# SoC_Supply_GND.net
KiCad netlist of a schematic drawn in Altium Designer
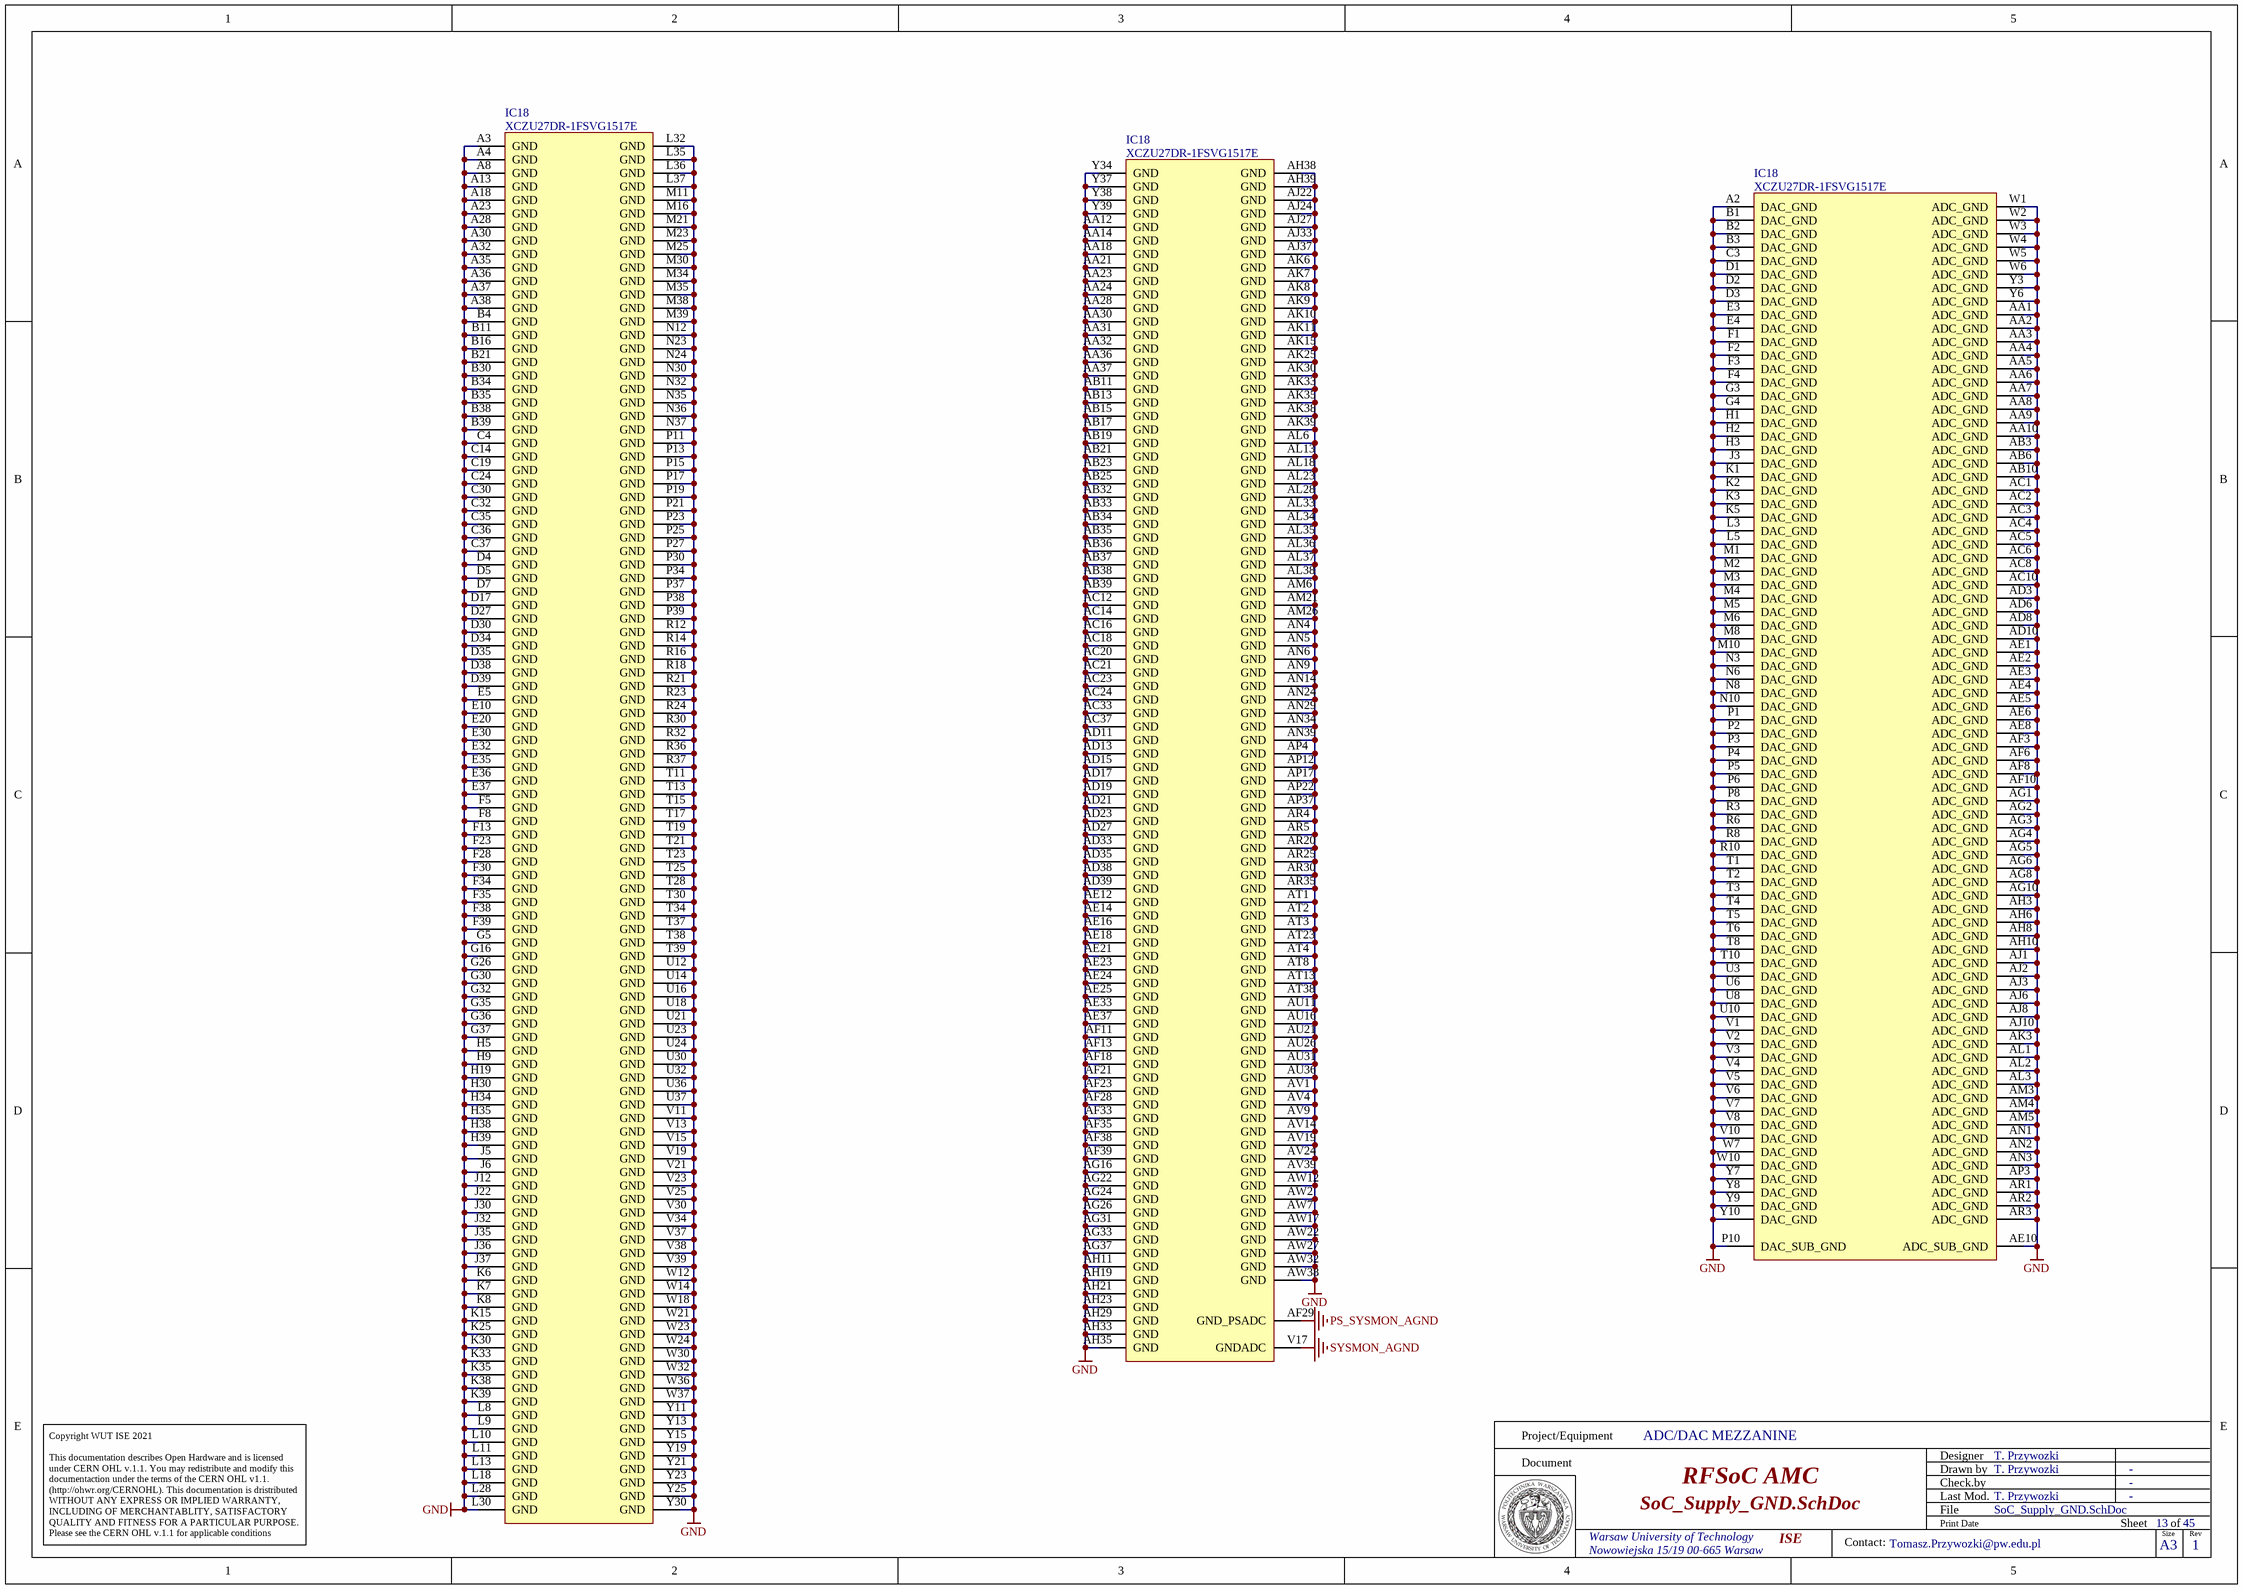
[diagram p0: SoC_Supply_GND.SchDoc]

(export (version "E")
  (design (tool "Eeschema 10.0.6"))
  (components
    (comp (ref "IC18")
      (value "XCZU27DR-1FSVG1517E")
      (footprint "XILINX_FSVG1517 (XCZU27DR)")
      (fields (field (name "MANUFACTURER") "XILINX") (field (name "AUTHOR") "CERN DEM MR"))
      (libsource (lib "ICs And Semiconductors") (part "XCZU27DR-1FSVG1517E"))
    )
  )
  (nets
    (net (code "1") (name "GND") (class "Default")
      (node (ref "IC18") (pin "A13") (pinfunction "GND_A13") (pintype "power_in"))
      (node (ref "IC18") (pin "A18") (pinfunction "GND_A18") (pintype "power_in"))
      (node (ref "IC18") (pin "A2") (pinfunction "DAC_GND_A2") (pintype "power_in"))
      (node (ref "IC18") (pin "A23") (pinfunction "GND_A23") (pintype "power_in"))
      (node (ref "IC18") (pin "A28") (pinfunction "GND_A28") (pintype "power_in"))
      (node (ref "IC18") (pin "A3") (pinfunction "GND_A3") (pintype "power_in"))
      (node (ref "IC18") (pin "A30") (pinfunction "GND_A30") (pintype "power_in"))
      (node (ref "IC18") (pin "A32") (pinfunction "GND_A32") (pintype "power_in"))
      (node (ref "IC18") (pin "A35") (pinfunction "GND_A35") (pintype "power_in"))
      (node (ref "IC18") (pin "A36") (pinfunction "GND_A36") (pintype "power_in"))
      (node (ref "IC18") (pin "A37") (pinfunction "GND_A37") (pintype "power_in"))
      (node (ref "IC18") (pin "A38") (pinfunction "GND_A38") (pintype "power_in"))
      (node (ref "IC18") (pin "A4") (pinfunction "GND_A4") (pintype "power_in"))
      (node (ref "IC18") (pin "A8") (pinfunction "GND_A8") (pintype "power_in"))
      (node (ref "IC18") (pin "AA1") (pinfunction "ADC_GND_AA1") (pintype "power_in"))
      (node (ref "IC18") (pin "AA10") (pinfunction "ADC_GND_AA10") (pintype "power_in"))
      (node (ref "IC18") (pin "AA12") (pinfunction "GND_AA12") (pintype "power_in"))
      (node (ref "IC18") (pin "AA14") (pinfunction "GND_AA14") (pintype "power_in"))
      (node (ref "IC18") (pin "AA18") (pinfunction "GND_AA18") (pintype "power_in"))
      (node (ref "IC18") (pin "AA2") (pinfunction "ADC_GND_AA2") (pintype "power_in"))
      (node (ref "IC18") (pin "AA21") (pinfunction "GND_AA21") (pintype "power_in"))
      (node (ref "IC18") (pin "AA23") (pinfunction "GND_AA23") (pintype "power_in"))
      (node (ref "IC18") (pin "AA24") (pinfunction "GND_AA24") (pintype "power_in"))
      (node (ref "IC18") (pin "AA28") (pinfunction "GND_AA28") (pintype "power_in"))
      (node (ref "IC18") (pin "AA3") (pinfunction "ADC_GND_AA3") (pintype "power_in"))
      (node (ref "IC18") (pin "AA30") (pinfunction "GND_AA30") (pintype "power_in"))
      (node (ref "IC18") (pin "AA31") (pinfunction "GND_AA31") (pintype "power_in"))
      (node (ref "IC18") (pin "AA32") (pinfunction "GND_AA32") (pintype "power_in"))
      (node (ref "IC18") (pin "AA36") (pinfunction "GND_AA36") (pintype "power_in"))
      (node (ref "IC18") (pin "AA37") (pinfunction "GND_AA37") (pintype "power_in"))
      (node (ref "IC18") (pin "AA4") (pinfunction "ADC_GND_AA4") (pintype "power_in"))
      (node (ref "IC18") (pin "AA5") (pinfunction "ADC_GND_AA5") (pintype "power_in"))
      (node (ref "IC18") (pin "AA6") (pinfunction "ADC_GND_AA6") (pintype "power_in"))
      (node (ref "IC18") (pin "AA7") (pinfunction "ADC_GND_AA7") (pintype "power_in"))
      (node (ref "IC18") (pin "AA8") (pinfunction "ADC_GND_AA8") (pintype "power_in"))
      (node (ref "IC18") (pin "AA9") (pinfunction "ADC_GND_AA9") (pintype "power_in"))
      (node (ref "IC18") (pin "AB10") (pinfunction "ADC_GND_AB10") (pintype "power_in"))
      (node (ref "IC18") (pin "AB11") (pinfunction "GND_AB11") (pintype "power_in"))
      (node (ref "IC18") (pin "AB13") (pinfunction "GND_AB13") (pintype "power_in"))
      (node (ref "IC18") (pin "AB15") (pinfunction "GND_AB15") (pintype "power_in"))
      (node (ref "IC18") (pin "AB17") (pinfunction "GND_AB17") (pintype "power_in"))
      (node (ref "IC18") (pin "AB19") (pinfunction "GND_AB19") (pintype "power_in"))
      (node (ref "IC18") (pin "AB21") (pinfunction "GND_AB21") (pintype "power_in"))
      (node (ref "IC18") (pin "AB23") (pinfunction "GND_AB23") (pintype "power_in"))
      (node (ref "IC18") (pin "AB25") (pinfunction "GND_AB25") (pintype "power_in"))
      (node (ref "IC18") (pin "AB3") (pinfunction "ADC_GND_AB3") (pintype "power_in"))
      (node (ref "IC18") (pin "AB32") (pinfunction "GND_AB32") (pintype "power_in"))
      (node (ref "IC18") (pin "AB33") (pinfunction "GND_AB33") (pintype "power_in"))
      (node (ref "IC18") (pin "AB34") (pinfunction "GND_AB34") (pintype "power_in"))
      (node (ref "IC18") (pin "AB35") (pinfunction "GND_AB35") (pintype "power_in"))
      (node (ref "IC18") (pin "AB36") (pinfunction "GND_AB36") (pintype "power_in"))
      (node (ref "IC18") (pin "AB37") (pinfunction "GND_AB37") (pintype "power_in"))
      (node (ref "IC18") (pin "AB38") (pinfunction "GND_AB38") (pintype "power_in"))
      (node (ref "IC18") (pin "AB39") (pinfunction "GND_AB39") (pintype "power_in"))
      (node (ref "IC18") (pin "AB6") (pinfunction "ADC_GND_AB6") (pintype "power_in"))
      (node (ref "IC18") (pin "AC1") (pinfunction "ADC_GND_AC1") (pintype "power_in"))
      (node (ref "IC18") (pin "AC10") (pinfunction "ADC_GND_AC10") (pintype "power_in"))
      (node (ref "IC18") (pin "AC12") (pinfunction "GND_AC12") (pintype "power_in"))
      (node (ref "IC18") (pin "AC14") (pinfunction "GND_AC14") (pintype "power_in"))
      (node (ref "IC18") (pin "AC16") (pinfunction "GND_AC16") (pintype "power_in"))
      (node (ref "IC18") (pin "AC18") (pinfunction "GND_AC18") (pintype "power_in"))
      (node (ref "IC18") (pin "AC2") (pinfunction "ADC_GND_AC2") (pintype "power_in"))
      (node (ref "IC18") (pin "AC20") (pinfunction "GND_AC20") (pintype "power_in"))
      (node (ref "IC18") (pin "AC21") (pinfunction "GND_AC21") (pintype "power_in"))
      (node (ref "IC18") (pin "AC23") (pinfunction "GND_AC23") (pintype "power_in"))
      (node (ref "IC18") (pin "AC24") (pinfunction "GND_AC24") (pintype "power_in"))
      (node (ref "IC18") (pin "AC3") (pinfunction "ADC_GND_AC3") (pintype "power_in"))
      (node (ref "IC18") (pin "AC33") (pinfunction "GND_AC33") (pintype "power_in"))
      (node (ref "IC18") (pin "AC37") (pinfunction "GND_AC37") (pintype "power_in"))
      (node (ref "IC18") (pin "AC4") (pinfunction "ADC_GND_AC4") (pintype "power_in"))
      (node (ref "IC18") (pin "AC5") (pinfunction "ADC_GND_AC5") (pintype "power_in"))
      (node (ref "IC18") (pin "AC6") (pinfunction "ADC_GND_AC6") (pintype "power_in"))
      (node (ref "IC18") (pin "AC8") (pinfunction "ADC_GND_AC8") (pintype "power_in"))
      (node (ref "IC18") (pin "AD10") (pinfunction "ADC_GND_AD10") (pintype "power_in"))
      (node (ref "IC18") (pin "AD11") (pinfunction "GND_AD11") (pintype "power_in"))
      (node (ref "IC18") (pin "AD13") (pinfunction "GND_AD13") (pintype "power_in"))
      (node (ref "IC18") (pin "AD15") (pinfunction "GND_AD15") (pintype "power_in"))
      (node (ref "IC18") (pin "AD17") (pinfunction "GND_AD17") (pintype "power_in"))
      (node (ref "IC18") (pin "AD19") (pinfunction "GND_AD19") (pintype "power_in"))
      (node (ref "IC18") (pin "AD21") (pinfunction "GND_AD21") (pintype "power_in"))
      (node (ref "IC18") (pin "AD23") (pinfunction "GND_AD23") (pintype "power_in"))
      (node (ref "IC18") (pin "AD27") (pinfunction "GND_AD27") (pintype "power_in"))
      (node (ref "IC18") (pin "AD3") (pinfunction "ADC_GND_AD3") (pintype "power_in"))
      (node (ref "IC18") (pin "AD33") (pinfunction "GND_AD33") (pintype "power_in"))
      (node (ref "IC18") (pin "AD35") (pinfunction "GND_AD35") (pintype "power_in"))
      (node (ref "IC18") (pin "AD38") (pinfunction "GND_AD38") (pintype "power_in"))
      (node (ref "IC18") (pin "AD39") (pinfunction "GND_AD39") (pintype "power_in"))
      (node (ref "IC18") (pin "AD6") (pinfunction "ADC_GND_AD6") (pintype "power_in"))
      (node (ref "IC18") (pin "AD8") (pinfunction "ADC_GND_AD8") (pintype "power_in"))
      (node (ref "IC18") (pin "AE1") (pinfunction "ADC_GND_AE1") (pintype "power_in"))
      (node (ref "IC18") (pin "AE10") (pinfunction "ADC_SUB_GND_AE10") (pintype "power_in"))
      (node (ref "IC18") (pin "AE12") (pinfunction "GND_AE12") (pintype "power_in"))
      (node (ref "IC18") (pin "AE14") (pinfunction "GND_AE14") (pintype "power_in"))
      (node (ref "IC18") (pin "AE16") (pinfunction "GND_AE16") (pintype "power_in"))
      (node (ref "IC18") (pin "AE18") (pinfunction "GND_AE18") (pintype "power_in"))
      (node (ref "IC18") (pin "AE2") (pinfunction "ADC_GND_AE2") (pintype "power_in"))
      (node (ref "IC18") (pin "AE21") (pinfunction "GND_AE21") (pintype "power_in"))
      (node (ref "IC18") (pin "AE23") (pinfunction "GND_AE23") (pintype "power_in"))
      (node (ref "IC18") (pin "AE24") (pinfunction "GND_AE24") (pintype "power_in"))
      (node (ref "IC18") (pin "AE25") (pinfunction "GND_AE25") (pintype "power_in"))
      (node (ref "IC18") (pin "AE3") (pinfunction "ADC_GND_AE3") (pintype "power_in"))
      (node (ref "IC18") (pin "AE33") (pinfunction "GND_AE33") (pintype "power_in"))
      (node (ref "IC18") (pin "AE37") (pinfunction "GND_AE37") (pintype "power_in"))
      (node (ref "IC18") (pin "AE4") (pinfunction "ADC_GND_AE4") (pintype "power_in"))
      (node (ref "IC18") (pin "AE5") (pinfunction "ADC_GND_AE5") (pintype "power_in"))
      (node (ref "IC18") (pin "AE6") (pinfunction "ADC_GND_AE6") (pintype "power_in"))
      (node (ref "IC18") (pin "AE8") (pinfunction "ADC_GND_AE8") (pintype "power_in"))
      (node (ref "IC18") (pin "AF10") (pinfunction "ADC_GND_AF10") (pintype "power_in"))
      (node (ref "IC18") (pin "AF11") (pinfunction "GND_AF11") (pintype "power_in"))
      (node (ref "IC18") (pin "AF13") (pinfunction "GND_AF13") (pintype "power_in"))
      (node (ref "IC18") (pin "AF18") (pinfunction "GND_AF18") (pintype "power_in"))
      (node (ref "IC18") (pin "AF21") (pinfunction "GND_AF21") (pintype "power_in"))
      (node (ref "IC18") (pin "AF23") (pinfunction "GND_AF23") (pintype "power_in"))
      (node (ref "IC18") (pin "AF28") (pinfunction "GND_AF28") (pintype "power_in"))
      (node (ref "IC18") (pin "AF3") (pinfunction "ADC_GND_AF3") (pintype "power_in"))
      (node (ref "IC18") (pin "AF33") (pinfunction "GND_AF33") (pintype "power_in"))
      (node (ref "IC18") (pin "AF35") (pinfunction "GND_AF35") (pintype "power_in"))
      (node (ref "IC18") (pin "AF38") (pinfunction "GND_AF38") (pintype "power_in"))
      (node (ref "IC18") (pin "AF39") (pinfunction "GND_AF39") (pintype "power_in"))
      (node (ref "IC18") (pin "AF6") (pinfunction "ADC_GND_AF6") (pintype "power_in"))
      (node (ref "IC18") (pin "AF8") (pinfunction "ADC_GND_AF8") (pintype "power_in"))
      (node (ref "IC18") (pin "AG1") (pinfunction "ADC_GND_AG1") (pintype "power_in"))
      (node (ref "IC18") (pin "AG10") (pinfunction "ADC_GND_AG10") (pintype "power_in"))
      (node (ref "IC18") (pin "AG16") (pinfunction "GND_AG16") (pintype "power_in"))
      (node (ref "IC18") (pin "AG2") (pinfunction "ADC_GND_AG2") (pintype "power_in"))
      (node (ref "IC18") (pin "AG22") (pinfunction "GND_AG22") (pintype "power_in"))
      (node (ref "IC18") (pin "AG24") (pinfunction "GND_AG24") (pintype "power_in"))
      (node (ref "IC18") (pin "AG26") (pinfunction "GND_AG26") (pintype "power_in"))
      (node (ref "IC18") (pin "AG3") (pinfunction "ADC_GND_AG3") (pintype "power_in"))
      (node (ref "IC18") (pin "AG31") (pinfunction "GND_AG31") (pintype "power_in"))
      (node (ref "IC18") (pin "AG33") (pinfunction "GND_AG33") (pintype "power_in"))
      (node (ref "IC18") (pin "AG37") (pinfunction "GND_AG37") (pintype "power_in"))
      (node (ref "IC18") (pin "AG4") (pinfunction "ADC_GND_AG4") (pintype "power_in"))
      (node (ref "IC18") (pin "AG5") (pinfunction "ADC_GND_AG5") (pintype "power_in"))
      (node (ref "IC18") (pin "AG6") (pinfunction "ADC_GND_AG6") (pintype "power_in"))
      (node (ref "IC18") (pin "AG8") (pinfunction "ADC_GND_AG8") (pintype "power_in"))
      (node (ref "IC18") (pin "AH10") (pinfunction "ADC_GND_AH10") (pintype "power_in"))
      (node (ref "IC18") (pin "AH11") (pinfunction "GND_AH11") (pintype "power_in"))
      (node (ref "IC18") (pin "AH19") (pinfunction "GND_AH19") (pintype "power_in"))
      (node (ref "IC18") (pin "AH21") (pinfunction "GND_AH21") (pintype "power_in"))
      (node (ref "IC18") (pin "AH23") (pinfunction "GND_AH23") (pintype "power_in"))
      (node (ref "IC18") (pin "AH29") (pinfunction "GND_AH29") (pintype "power_in"))
      (node (ref "IC18") (pin "AH3") (pinfunction "ADC_GND_AH3") (pintype "power_in"))
      (node (ref "IC18") (pin "AH33") (pinfunction "GND_AH33") (pintype "power_in"))
      (node (ref "IC18") (pin "AH35") (pinfunction "GND_AH35") (pintype "power_in"))
      (node (ref "IC18") (pin "AH38") (pinfunction "GND_AH38") (pintype "power_in"))
      (node (ref "IC18") (pin "AH39") (pinfunction "GND_AH39") (pintype "power_in"))
      (node (ref "IC18") (pin "AH6") (pinfunction "ADC_GND_AH6") (pintype "power_in"))
      (node (ref "IC18") (pin "AH8") (pinfunction "ADC_GND_AH8") (pintype "power_in"))
      (node (ref "IC18") (pin "AJ1") (pinfunction "ADC_GND_AJ1") (pintype "power_in"))
      (node (ref "IC18") (pin "AJ10") (pinfunction "ADC_GND_AJ10") (pintype "power_in"))
      (node (ref "IC18") (pin "AJ2") (pinfunction "ADC_GND_AJ2") (pintype "power_in"))
      (node (ref "IC18") (pin "AJ22") (pinfunction "GND_AJ22") (pintype "power_in"))
      (node (ref "IC18") (pin "AJ24") (pinfunction "GND_AJ24") (pintype "power_in"))
      (node (ref "IC18") (pin "AJ27") (pinfunction "GND_AJ27") (pintype "power_in"))
      (node (ref "IC18") (pin "AJ3") (pinfunction "ADC_GND_AJ3") (pintype "power_in"))
      (node (ref "IC18") (pin "AJ33") (pinfunction "GND_AJ33") (pintype "power_in"))
      (node (ref "IC18") (pin "AJ37") (pinfunction "GND_AJ37") (pintype "power_in"))
      (node (ref "IC18") (pin "AJ6") (pinfunction "ADC_GND_AJ6") (pintype "power_in"))
      (node (ref "IC18") (pin "AJ8") (pinfunction "ADC_GND_AJ8") (pintype "power_in"))
      (node (ref "IC18") (pin "AK10") (pinfunction "GND_AK10") (pintype "power_in"))
      (node (ref "IC18") (pin "AK11") (pinfunction "GND_AK11") (pintype "power_in"))
      (node (ref "IC18") (pin "AK15") (pinfunction "GND_AK15") (pintype "power_in"))
      (node (ref "IC18") (pin "AK25") (pinfunction "GND_AK25") (pintype "power_in"))
      (node (ref "IC18") (pin "AK3") (pinfunction "ADC_GND_AK3") (pintype "power_in"))
      (node (ref "IC18") (pin "AK30") (pinfunction "GND_AK30") (pintype "power_in"))
      (node (ref "IC18") (pin "AK33") (pinfunction "GND_AK33") (pintype "power_in"))
      (node (ref "IC18") (pin "AK35") (pinfunction "GND_AK35") (pintype "power_in"))
      (node (ref "IC18") (pin "AK38") (pinfunction "GND_AK38") (pintype "power_in"))
      (node (ref "IC18") (pin "AK39") (pinfunction "GND_AK39") (pintype "power_in"))
      (node (ref "IC18") (pin "AK6") (pinfunction "GND_AK6") (pintype "power_in"))
      (node (ref "IC18") (pin "AK7") (pinfunction "GND_AK7") (pintype "power_in"))
      (node (ref "IC18") (pin "AK8") (pinfunction "GND_AK8") (pintype "power_in"))
      (node (ref "IC18") (pin "AK9") (pinfunction "GND_AK9") (pintype "power_in"))
      (node (ref "IC18") (pin "AL1") (pinfunction "ADC_GND_AL1") (pintype "power_in"))
      (node (ref "IC18") (pin "AL13") (pinfunction "GND_AL13") (pintype "power_in"))
      (node (ref "IC18") (pin "AL18") (pinfunction "GND_AL18") (pintype "power_in"))
      (node (ref "IC18") (pin "AL2") (pinfunction "ADC_GND_AL2") (pintype "power_in"))
      (node (ref "IC18") (pin "AL23") (pinfunction "GND_AL23") (pintype "power_in"))
      (node (ref "IC18") (pin "AL28") (pinfunction "GND_AL28") (pintype "power_in"))
      (node (ref "IC18") (pin "AL3") (pinfunction "ADC_GND_AL3") (pintype "power_in"))
      (node (ref "IC18") (pin "AL33") (pinfunction "GND_AL33") (pintype "power_in"))
      (node (ref "IC18") (pin "AL34") (pinfunction "GND_AL34") (pintype "power_in"))
      (node (ref "IC18") (pin "AL35") (pinfunction "GND_AL35") (pintype "power_in"))
      (node (ref "IC18") (pin "AL36") (pinfunction "GND_AL36") (pintype "power_in"))
      (node (ref "IC18") (pin "AL37") (pinfunction "GND_AL37") (pintype "power_in"))
      (node (ref "IC18") (pin "AL38") (pinfunction "GND_AL38") (pintype "power_in"))
      (node (ref "IC18") (pin "AL6") (pinfunction "GND_AL6") (pintype "power_in"))
      (node (ref "IC18") (pin "AM21") (pinfunction "GND_AM21") (pintype "power_in"))
      (node (ref "IC18") (pin "AM26") (pinfunction "GND_AM26") (pintype "power_in"))
      (node (ref "IC18") (pin "AM3") (pinfunction "ADC_GND_AM3") (pintype "power_in"))
      (node (ref "IC18") (pin "AM4") (pinfunction "ADC_GND_AM4") (pintype "power_in"))
      (node (ref "IC18") (pin "AM5") (pinfunction "ADC_GND_AM5") (pintype "power_in"))
      (node (ref "IC18") (pin "AM6") (pinfunction "GND_AM6") (pintype "power_in"))
      (node (ref "IC18") (pin "AN1") (pinfunction "ADC_GND_AN1") (pintype "power_in"))
      (node (ref "IC18") (pin "AN14") (pinfunction "GND_AN14") (pintype "power_in"))
      (node (ref "IC18") (pin "AN2") (pinfunction "ADC_GND_AN2") (pintype "power_in"))
      (node (ref "IC18") (pin "AN24") (pinfunction "GND_AN24") (pintype "power_in"))
      (node (ref "IC18") (pin "AN29") (pinfunction "GND_AN29") (pintype "power_in"))
      (node (ref "IC18") (pin "AN3") (pinfunction "ADC_GND_AN3") (pintype "power_in"))
      (node (ref "IC18") (pin "AN34") (pinfunction "GND_AN34") (pintype "power_in"))
      (node (ref "IC18") (pin "AN39") (pinfunction "GND_AN39") (pintype "power_in"))
      (node (ref "IC18") (pin "AN4") (pinfunction "GND_AN4") (pintype "power_in"))
      (node (ref "IC18") (pin "AN5") (pinfunction "GND_AN5") (pintype "power_in"))
      (node (ref "IC18") (pin "AN6") (pinfunction "GND_AN6") (pintype "power_in"))
      (node (ref "IC18") (pin "AN9") (pinfunction "GND_AN9") (pintype "power_in"))
      (node (ref "IC18") (pin "AP12") (pinfunction "GND_AP12") (pintype "power_in"))
      (node (ref "IC18") (pin "AP17") (pinfunction "GND_AP17") (pintype "power_in"))
      (node (ref "IC18") (pin "AP22") (pinfunction "GND_AP22") (pintype "power_in"))
      (node (ref "IC18") (pin "AP3") (pinfunction "ADC_GND_AP3") (pintype "power_in"))
      (node (ref "IC18") (pin "AP37") (pinfunction "GND_AP37") (pintype "power_in"))
      (node (ref "IC18") (pin "AP4") (pinfunction "GND_AP4") (pintype "power_in"))
      (node (ref "IC18") (pin "AR1") (pinfunction "ADC_GND_AR1") (pintype "power_in"))
      (node (ref "IC18") (pin "AR2") (pinfunction "ADC_GND_AR2") (pintype "power_in"))
      (node (ref "IC18") (pin "AR20") (pinfunction "GND_AR20") (pintype "power_in"))
      (node (ref "IC18") (pin "AR25") (pinfunction "GND_AR25") (pintype "power_in"))
      (node (ref "IC18") (pin "AR3") (pinfunction "ADC_GND_AR3") (pintype "power_in"))
      (node (ref "IC18") (pin "AR30") (pinfunction "GND_AR30") (pintype "power_in"))
      (node (ref "IC18") (pin "AR35") (pinfunction "GND_AR35") (pintype "power_in"))
      (node (ref "IC18") (pin "AR4") (pinfunction "GND_AR4") (pintype "power_in"))
      (node (ref "IC18") (pin "AR5") (pinfunction "GND_AR5") (pintype "power_in"))
      (node (ref "IC18") (pin "AT1") (pinfunction "GND_AT1") (pintype "power_in"))
      (node (ref "IC18") (pin "AT13") (pinfunction "GND_AT13") (pintype "power_in"))
      (node (ref "IC18") (pin "AT2") (pinfunction "GND_AT2") (pintype "power_in"))
      (node (ref "IC18") (pin "AT23") (pinfunction "GND_AT23") (pintype "power_in"))
      (node (ref "IC18") (pin "AT3") (pinfunction "GND_AT3") (pintype "power_in"))
      (node (ref "IC18") (pin "AT38") (pinfunction "GND_AT38") (pintype "power_in"))
      (node (ref "IC18") (pin "AT4") (pinfunction "GND_AT4") (pintype "power_in"))
      (node (ref "IC18") (pin "AT8") (pinfunction "GND_AT8") (pintype "power_in"))
      (node (ref "IC18") (pin "AU11") (pinfunction "GND_AU11") (pintype "power_in"))
      (node (ref "IC18") (pin "AU16") (pinfunction "GND_AU16") (pintype "power_in"))
      (node (ref "IC18") (pin "AU21") (pinfunction "GND_AU21") (pintype "power_in"))
      (node (ref "IC18") (pin "AU26") (pinfunction "GND_AU26") (pintype "power_in"))
      (node (ref "IC18") (pin "AU31") (pinfunction "GND_AU31") (pintype "power_in"))
      (node (ref "IC18") (pin "AU36") (pinfunction "GND_AU36") (pintype "power_in"))
      (node (ref "IC18") (pin "AV1") (pinfunction "GND_AV1") (pintype "power_in"))
      (node (ref "IC18") (pin "AV14") (pinfunction "GND_AV14") (pintype "power_in"))
      (node (ref "IC18") (pin "AV19") (pinfunction "GND_AV19") (pintype "power_in"))
      (node (ref "IC18") (pin "AV24") (pinfunction "GND_AV24") (pintype "power_in"))
      (node (ref "IC18") (pin "AV39") (pinfunction "GND_AV39") (pintype "power_in"))
      (node (ref "IC18") (pin "AV4") (pinfunction "GND_AV4") (pintype "power_in"))
      (node (ref "IC18") (pin "AV9") (pinfunction "GND_AV9") (pintype "power_in"))
      (node (ref "IC18") (pin "AW12") (pinfunction "GND_AW12") (pintype "power_in"))
      (node (ref "IC18") (pin "AW17") (pinfunction "GND_AW17") (pintype "power_in"))
      (node (ref "IC18") (pin "AW2") (pinfunction "GND_AW2") (pintype "power_in"))
      (node (ref "IC18") (pin "AW22") (pinfunction "GND_AW22") (pintype "power_in"))
      (node (ref "IC18") (pin "AW27") (pinfunction "GND_AW27") (pintype "power_in"))
      (node (ref "IC18") (pin "AW32") (pinfunction "GND_AW32") (pintype "power_in"))
      (node (ref "IC18") (pin "AW38") (pinfunction "GND_AW38") (pintype "power_in"))
      (node (ref "IC18") (pin "AW7") (pinfunction "GND_AW7") (pintype "power_in"))
      (node (ref "IC18") (pin "B1") (pinfunction "DAC_GND_B1") (pintype "power_in"))
      (node (ref "IC18") (pin "B11") (pinfunction "GND_B11") (pintype "power_in"))
      (node (ref "IC18") (pin "B16") (pinfunction "GND_B16") (pintype "power_in"))
      (node (ref "IC18") (pin "B2") (pinfunction "DAC_GND_B2") (pintype "power_in"))
      (node (ref "IC18") (pin "B21") (pinfunction "GND_B21") (pintype "power_in"))
      (node (ref "IC18") (pin "B3") (pinfunction "DAC_GND_B3") (pintype "power_in"))
      (node (ref "IC18") (pin "B30") (pinfunction "GND_B30") (pintype "power_in"))
      (node (ref "IC18") (pin "B34") (pinfunction "GND_B34") (pintype "power_in"))
      (node (ref "IC18") (pin "B35") (pinfunction "GND_B35") (pintype "power_in"))
      (node (ref "IC18") (pin "B38") (pinfunction "GND_B38") (pintype "power_in"))
      (node (ref "IC18") (pin "B39") (pinfunction "GND_B39") (pintype "power_in"))
      (node (ref "IC18") (pin "B4") (pinfunction "GND_B4") (pintype "power_in"))
      (node (ref "IC18") (pin "C14") (pinfunction "GND_C14") (pintype "power_in"))
      (node (ref "IC18") (pin "C19") (pinfunction "GND_C19") (pintype "power_in"))
      (node (ref "IC18") (pin "C24") (pinfunction "GND_C24") (pintype "power_in"))
      (node (ref "IC18") (pin "C3") (pinfunction "DAC_GND_C3") (pintype "power_in"))
      (node (ref "IC18") (pin "C30") (pinfunction "GND_C30") (pintype "power_in"))
      (node (ref "IC18") (pin "C32") (pinfunction "GND_C32") (pintype "power_in"))
      (node (ref "IC18") (pin "C35") (pinfunction "GND_C35") (pintype "power_in"))
      (node (ref "IC18") (pin "C36") (pinfunction "GND_C36") (pintype "power_in"))
      (node (ref "IC18") (pin "C37") (pinfunction "GND_C37") (pintype "power_in"))
      (node (ref "IC18") (pin "C4") (pinfunction "GND_C4") (pintype "power_in"))
      (node (ref "IC18") (pin "D1") (pinfunction "DAC_GND_D1") (pintype "power_in"))
      (node (ref "IC18") (pin "D17") (pinfunction "GND_D17") (pintype "power_in"))
      (node (ref "IC18") (pin "D2") (pinfunction "DAC_GND_D2") (pintype "power_in"))
      (node (ref "IC18") (pin "D27") (pinfunction "GND_D27") (pintype "power_in"))
      (node (ref "IC18") (pin "D3") (pinfunction "DAC_GND_D3") (pintype "power_in"))
      (node (ref "IC18") (pin "D30") (pinfunction "GND_D30") (pintype "power_in"))
      (node (ref "IC18") (pin "D34") (pinfunction "GND_D34") (pintype "power_in"))
      (node (ref "IC18") (pin "D35") (pinfunction "GND_D35") (pintype "power_in"))
      (node (ref "IC18") (pin "D38") (pinfunction "GND_D38") (pintype "power_in"))
      (node (ref "IC18") (pin "D39") (pinfunction "GND_D39") (pintype "power_in"))
      (node (ref "IC18") (pin "D4") (pinfunction "GND_D4") (pintype "power_in"))
      (node (ref "IC18") (pin "D5") (pinfunction "GND_D5") (pintype "power_in"))
      (node (ref "IC18") (pin "D7") (pinfunction "GND_D7") (pintype "power_in"))
      (node (ref "IC18") (pin "E10") (pinfunction "GND_E10") (pintype "power_in"))
      (node (ref "IC18") (pin "E20") (pinfunction "GND_E20") (pintype "power_in"))
      (node (ref "IC18") (pin "E3") (pinfunction "DAC_GND_E3") (pintype "power_in"))
      (node (ref "IC18") (pin "E30") (pinfunction "GND_E30") (pintype "power_in"))
      (node (ref "IC18") (pin "E32") (pinfunction "GND_E32") (pintype "power_in"))
      (node (ref "IC18") (pin "E35") (pinfunction "GND_E35") (pintype "power_in"))
      (node (ref "IC18") (pin "E36") (pinfunction "GND_E36") (pintype "power_in"))
      (node (ref "IC18") (pin "E37") (pinfunction "GND_E37") (pintype "power_in"))
      (node (ref "IC18") (pin "E4") (pinfunction "DAC_GND_E4") (pintype "power_in"))
      (node (ref "IC18") (pin "E5") (pinfunction "GND_E5") (pintype "power_in"))
      (node (ref "IC18") (pin "F1") (pinfunction "DAC_GND_F1") (pintype "power_in"))
      (node (ref "IC18") (pin "F13") (pinfunction "GND_F13") (pintype "power_in"))
      (node (ref "IC18") (pin "F2") (pinfunction "DAC_GND_F2") (pintype "power_in"))
      (node (ref "IC18") (pin "F23") (pinfunction "GND_F23") (pintype "power_in"))
      (node (ref "IC18") (pin "F28") (pinfunction "GND_F28") (pintype "power_in"))
      (node (ref "IC18") (pin "F3") (pinfunction "DAC_GND_F3") (pintype "power_in"))
      (node (ref "IC18") (pin "F30") (pinfunction "GND_F30") (pintype "power_in"))
      (node (ref "IC18") (pin "F34") (pinfunction "GND_F34") (pintype "power_in"))
      (node (ref "IC18") (pin "F35") (pinfunction "GND_F35") (pintype "power_in"))
      (node (ref "IC18") (pin "F38") (pinfunction "GND_F38") (pintype "power_in"))
      (node (ref "IC18") (pin "F39") (pinfunction "GND_F39") (pintype "power_in"))
      (node (ref "IC18") (pin "F4") (pinfunction "DAC_GND_F4") (pintype "power_in"))
      (node (ref "IC18") (pin "F5") (pinfunction "GND_F5") (pintype "power_in"))
      (node (ref "IC18") (pin "F8") (pinfunction "GND_F8") (pintype "power_in"))
      (node (ref "IC18") (pin "G16") (pinfunction "GND_G16") (pintype "power_in"))
      (node (ref "IC18") (pin "G26") (pinfunction "GND_G26") (pintype "power_in"))
      (node (ref "IC18") (pin "G3") (pinfunction "DAC_GND_G3") (pintype "power_in"))
      (node (ref "IC18") (pin "G30") (pinfunction "GND_G30") (pintype "power_in"))
      (node (ref "IC18") (pin "G32") (pinfunction "GND_G32") (pintype "power_in"))
      (node (ref "IC18") (pin "G35") (pinfunction "GND_G35") (pintype "power_in"))
      (node (ref "IC18") (pin "G36") (pinfunction "GND_G36") (pintype "power_in"))
      (node (ref "IC18") (pin "G37") (pinfunction "GND_G37") (pintype "power_in"))
      (node (ref "IC18") (pin "G4") (pinfunction "DAC_GND_G4") (pintype "power_in"))
      (node (ref "IC18") (pin "G5") (pinfunction "GND_G5") (pintype "power_in"))
      (node (ref "IC18") (pin "H1") (pinfunction "DAC_GND_H1") (pintype "power_in"))
      (node (ref "IC18") (pin "H19") (pinfunction "GND_H19") (pintype "power_in"))
      (node (ref "IC18") (pin "H2") (pinfunction "DAC_GND_H2") (pintype "power_in"))
      (node (ref "IC18") (pin "H3") (pinfunction "DAC_GND_H3") (pintype "power_in"))
      (node (ref "IC18") (pin "H30") (pinfunction "GND_H30") (pintype "power_in"))
      (node (ref "IC18") (pin "H34") (pinfunction "GND_H34") (pintype "power_in"))
      (node (ref "IC18") (pin "H35") (pinfunction "GND_H35") (pintype "power_in"))
      (node (ref "IC18") (pin "H38") (pinfunction "GND_H38") (pintype "power_in"))
      (node (ref "IC18") (pin "H39") (pinfunction "GND_H39") (pintype "power_in"))
      (node (ref "IC18") (pin "H5") (pinfunction "GND_H5") (pintype "power_in"))
      (node (ref "IC18") (pin "H9") (pinfunction "GND_H9") (pintype "power_in"))
      (node (ref "IC18") (pin "J12") (pinfunction "GND_J12") (pintype "power_in"))
      (node (ref "IC18") (pin "J22") (pinfunction "GND_J22") (pintype "power_in"))
      (node (ref "IC18") (pin "J3") (pinfunction "DAC_GND_J3") (pintype "power_in"))
      (node (ref "IC18") (pin "J30") (pinfunction "GND_J30") (pintype "power_in"))
      (node (ref "IC18") (pin "J32") (pinfunction "GND_J32") (pintype "power_in"))
      (node (ref "IC18") (pin "J35") (pinfunction "GND_J35") (pintype "power_in"))
      (node (ref "IC18") (pin "J36") (pinfunction "GND_J36") (pintype "power_in"))
      (node (ref "IC18") (pin "J37") (pinfunction "GND_J37") (pintype "power_in"))
      (node (ref "IC18") (pin "J5") (pinfunction "GND_J5") (pintype "power_in"))
      (node (ref "IC18") (pin "J6") (pinfunction "GND_J6") (pintype "power_in"))
      (node (ref "IC18") (pin "K1") (pinfunction "DAC_GND_K1") (pintype "power_in"))
      (node (ref "IC18") (pin "K15") (pinfunction "GND_K15") (pintype "power_in"))
      (node (ref "IC18") (pin "K2") (pinfunction "DAC_GND_K2") (pintype "power_in"))
      (node (ref "IC18") (pin "K25") (pinfunction "GND_K25") (pintype "power_in"))
      (node (ref "IC18") (pin "K3") (pinfunction "DAC_GND_K3") (pintype "power_in"))
      (node (ref "IC18") (pin "K30") (pinfunction "GND_K30") (pintype "power_in"))
      (node (ref "IC18") (pin "K33") (pinfunction "GND_K33") (pintype "power_in"))
      (node (ref "IC18") (pin "K35") (pinfunction "GND_K35") (pintype "power_in"))
      (node (ref "IC18") (pin "K38") (pinfunction "GND_K38") (pintype "power_in"))
      (node (ref "IC18") (pin "K39") (pinfunction "GND_K39") (pintype "power_in"))
      (node (ref "IC18") (pin "K5") (pinfunction "DAC_GND_K5") (pintype "power_in"))
      (node (ref "IC18") (pin "K6") (pinfunction "GND_K6") (pintype "power_in"))
      (node (ref "IC18") (pin "K7") (pinfunction "GND_K7") (pintype "power_in"))
      (node (ref "IC18") (pin "K8") (pinfunction "GND_K8") (pintype "power_in"))
      (node (ref "IC18") (pin "L10") (pinfunction "GND_L10") (pintype "power_in"))
      (node (ref "IC18") (pin "L11") (pinfunction "GND_L11") (pintype "power_in"))
      (node (ref "IC18") (pin "L13") (pinfunction "GND_L13") (pintype "power_in"))
      (node (ref "IC18") (pin "L18") (pinfunction "GND_L18") (pintype "power_in"))
      (node (ref "IC18") (pin "L28") (pinfunction "GND_L28") (pintype "power_in"))
      (node (ref "IC18") (pin "L3") (pinfunction "DAC_GND_L3") (pintype "power_in"))
      (node (ref "IC18") (pin "L30") (pinfunction "GND_L30") (pintype "power_in"))
      (node (ref "IC18") (pin "L32") (pinfunction "GND_L32") (pintype "power_in"))
      (node (ref "IC18") (pin "L35") (pinfunction "GND_L35") (pintype "power_in"))
      (node (ref "IC18") (pin "L36") (pinfunction "GND_L36") (pintype "power_in"))
      (node (ref "IC18") (pin "L37") (pinfunction "GND_L37") (pintype "power_in"))
      (node (ref "IC18") (pin "L5") (pinfunction "DAC_GND_L5") (pintype "power_in"))
      (node (ref "IC18") (pin "L8") (pinfunction "GND_L8") (pintype "power_in"))
      (node (ref "IC18") (pin "L9") (pinfunction "GND_L9") (pintype "power_in"))
      (node (ref "IC18") (pin "M1") (pinfunction "DAC_GND_M1") (pintype "power_in"))
      (node (ref "IC18") (pin "M10") (pinfunction "DAC_GND_M10") (pintype "power_in"))
      (node (ref "IC18") (pin "M11") (pinfunction "GND_M11") (pintype "power_in"))
      (node (ref "IC18") (pin "M16") (pinfunction "GND_M16") (pintype "power_in"))
      (node (ref "IC18") (pin "M2") (pinfunction "DAC_GND_M2") (pintype "power_in"))
      (node (ref "IC18") (pin "M21") (pinfunction "GND_M21") (pintype "power_in"))
      (node (ref "IC18") (pin "M23") (pinfunction "GND_M23") (pintype "power_in"))
      (node (ref "IC18") (pin "M25") (pinfunction "GND_M25") (pintype "power_in"))
      (node (ref "IC18") (pin "M3") (pinfunction "DAC_GND_M3") (pintype "power_in"))
      (node (ref "IC18") (pin "M30") (pinfunction "GND_M30") (pintype "power_in"))
      (node (ref "IC18") (pin "M34") (pinfunction "GND_M34") (pintype "power_in"))
      (node (ref "IC18") (pin "M35") (pinfunction "GND_M35") (pintype "power_in"))
      (node (ref "IC18") (pin "M38") (pinfunction "GND_M38") (pintype "power_in"))
      (node (ref "IC18") (pin "M39") (pinfunction "GND_M39") (pintype "power_in"))
      (node (ref "IC18") (pin "M4") (pinfunction "DAC_GND_M4") (pintype "power_in"))
      (node (ref "IC18") (pin "M5") (pinfunction "DAC_GND_M5") (pintype "power_in"))
      (node (ref "IC18") (pin "M6") (pinfunction "DAC_GND_M6") (pintype "power_in"))
      (node (ref "IC18") (pin "M8") (pinfunction "DAC_GND_M8") (pintype "power_in"))
      (node (ref "IC18") (pin "N10") (pinfunction "DAC_GND_N10") (pintype "power_in"))
      (node (ref "IC18") (pin "N12") (pinfunction "GND_N12") (pintype "power_in"))
      (node (ref "IC18") (pin "N23") (pinfunction "GND_N23") (pintype "power_in"))
      (node (ref "IC18") (pin "N24") (pinfunction "GND_N24") (pintype "power_in"))
      (node (ref "IC18") (pin "N3") (pinfunction "DAC_GND_N3") (pintype "power_in"))
      (node (ref "IC18") (pin "N30") (pinfunction "GND_N30") (pintype "power_in"))
      (node (ref "IC18") (pin "N32") (pinfunction "GND_N32") (pintype "power_in"))
      (node (ref "IC18") (pin "N35") (pinfunction "GND_N35") (pintype "power_in"))
      (node (ref "IC18") (pin "N36") (pinfunction "GND_N36") (pintype "power_in"))
      (node (ref "IC18") (pin "N37") (pinfunction "GND_N37") (pintype "power_in"))
      (node (ref "IC18") (pin "N6") (pinfunction "DAC_GND_N6") (pintype "power_in"))
      (node (ref "IC18") (pin "N8") (pinfunction "DAC_GND_N8") (pintype "power_in"))
      (node (ref "IC18") (pin "P1") (pinfunction "DAC_GND_P1") (pintype "power_in"))
      (node (ref "IC18") (pin "P10") (pinfunction "DAC_SUB_GND_P10") (pintype "power_in"))
      (node (ref "IC18") (pin "P11") (pinfunction "GND_P11") (pintype "power_in"))
      (node (ref "IC18") (pin "P13") (pinfunction "GND_P13") (pintype "power_in"))
      (node (ref "IC18") (pin "P15") (pinfunction "GND_P15") (pintype "power_in"))
      (node (ref "IC18") (pin "P17") (pinfunction "GND_P17") (pintype "power_in"))
      (node (ref "IC18") (pin "P19") (pinfunction "GND_P19") (pintype "power_in"))
      (node (ref "IC18") (pin "P2") (pinfunction "DAC_GND_P2") (pintype "power_in"))
      (node (ref "IC18") (pin "P21") (pinfunction "GND_P21") (pintype "power_in"))
      (node (ref "IC18") (pin "P23") (pinfunction "GND_P23") (pintype "power_in"))
      (node (ref "IC18") (pin "P25") (pinfunction "GND_P25") (pintype "power_in"))
      (node (ref "IC18") (pin "P27") (pinfunction "GND_P27") (pintype "power_in"))
      (node (ref "IC18") (pin "P3") (pinfunction "DAC_GND_P3") (pintype "power_in"))
      (node (ref "IC18") (pin "P30") (pinfunction "GND_P30") (pintype "power_in"))
      (node (ref "IC18") (pin "P34") (pinfunction "GND_P34") (pintype "power_in"))
      (node (ref "IC18") (pin "P37") (pinfunction "GND_P37") (pintype "power_in"))
      (node (ref "IC18") (pin "P38") (pinfunction "GND_P38") (pintype "power_in"))
      (node (ref "IC18") (pin "P39") (pinfunction "GND_P39") (pintype "power_in"))
      (node (ref "IC18") (pin "P4") (pinfunction "DAC_GND_P4") (pintype "power_in"))
      (node (ref "IC18") (pin "P5") (pinfunction "DAC_GND_P5") (pintype "power_in"))
      (node (ref "IC18") (pin "P6") (pinfunction "DAC_GND_P6") (pintype "power_in"))
      (node (ref "IC18") (pin "P8") (pinfunction "DAC_GND_P8") (pintype "power_in"))
      (node (ref "IC18") (pin "R10") (pinfunction "DAC_GND_R10") (pintype "power_in"))
      (node (ref "IC18") (pin "R12") (pinfunction "GND_R12") (pintype "power_in"))
      (node (ref "IC18") (pin "R14") (pinfunction "GND_R14") (pintype "power_in"))
      (node (ref "IC18") (pin "R16") (pinfunction "GND_R16") (pintype "power_in"))
      (node (ref "IC18") (pin "R18") (pinfunction "GND_R18") (pintype "power_in"))
      (node (ref "IC18") (pin "R21") (pinfunction "GND_R21") (pintype "power_in"))
      (node (ref "IC18") (pin "R23") (pinfunction "GND_R23") (pintype "power_in"))
      (node (ref "IC18") (pin "R24") (pinfunction "GND_R24") (pintype "power_in"))
      (node (ref "IC18") (pin "R3") (pinfunction "DAC_GND_R3") (pintype "power_in"))
      (node (ref "IC18") (pin "R30") (pinfunction "GND_R30") (pintype "power_in"))
      (node (ref "IC18") (pin "R32") (pinfunction "GND_R32") (pintype "power_in"))
      (node (ref "IC18") (pin "R36") (pinfunction "GND_R36") (pintype "power_in"))
      (node (ref "IC18") (pin "R37") (pinfunction "GND_R37") (pintype "power_in"))
      (node (ref "IC18") (pin "R6") (pinfunction "DAC_GND_R6") (pintype "power_in"))
      (node (ref "IC18") (pin "R8") (pinfunction "DAC_GND_R8") (pintype "power_in"))
      (node (ref "IC18") (pin "T1") (pinfunction "DAC_GND_T1") (pintype "power_in"))
      (node (ref "IC18") (pin "T10") (pinfunction "DAC_GND_T10") (pintype "power_in"))
      (node (ref "IC18") (pin "T11") (pinfunction "GND_T11") (pintype "power_in"))
      (node (ref "IC18") (pin "T13") (pinfunction "GND_T13") (pintype "power_in"))
      (node (ref "IC18") (pin "T15") (pinfunction "GND_T15") (pintype "power_in"))
      (node (ref "IC18") (pin "T17") (pinfunction "GND_T17") (pintype "power_in"))
      (node (ref "IC18") (pin "T19") (pinfunction "GND_T19") (pintype "power_in"))
      (node (ref "IC18") (pin "T2") (pinfunction "DAC_GND_T2") (pintype "power_in"))
      (node (ref "IC18") (pin "T21") (pinfunction "GND_T21") (pintype "power_in"))
      (node (ref "IC18") (pin "T23") (pinfunction "GND_T23") (pintype "power_in"))
      (node (ref "IC18") (pin "T25") (pinfunction "GND_T25") (pintype "power_in"))
      (node (ref "IC18") (pin "T28") (pinfunction "GND_T28") (pintype "power_in"))
      (node (ref "IC18") (pin "T3") (pinfunction "DAC_GND_T3") (pintype "power_in"))
      (node (ref "IC18") (pin "T30") (pinfunction "GND_T30") (pintype "power_in"))
      (node (ref "IC18") (pin "T34") (pinfunction "GND_T34") (pintype "power_in"))
      (node (ref "IC18") (pin "T37") (pinfunction "GND_T37") (pintype "power_in"))
      (node (ref "IC18") (pin "T38") (pinfunction "GND_T38") (pintype "power_in"))
      (node (ref "IC18") (pin "T39") (pinfunction "GND_T39") (pintype "power_in"))
      (node (ref "IC18") (pin "T4") (pinfunction "DAC_GND_T4") (pintype "power_in"))
      (node (ref "IC18") (pin "T5") (pinfunction "DAC_GND_T5") (pintype "power_in"))
      (node (ref "IC18") (pin "T6") (pinfunction "DAC_GND_T6") (pintype "power_in"))
      (node (ref "IC18") (pin "T8") (pinfunction "DAC_GND_T8") (pintype "power_in"))
      (node (ref "IC18") (pin "U10") (pinfunction "DAC_GND_U10") (pintype "power_in"))
      (node (ref "IC18") (pin "U12") (pinfunction "GND_U12") (pintype "power_in"))
      (node (ref "IC18") (pin "U14") (pinfunction "GND_U14") (pintype "power_in"))
      (node (ref "IC18") (pin "U16") (pinfunction "GND_U16") (pintype "power_in"))
      (node (ref "IC18") (pin "U18") (pinfunction "GND_U18") (pintype "power_in"))
      (node (ref "IC18") (pin "U21") (pinfunction "GND_U21") (pintype "power_in"))
      (node (ref "IC18") (pin "U23") (pinfunction "GND_U23") (pintype "power_in"))
      (node (ref "IC18") (pin "U24") (pinfunction "GND_U24") (pintype "power_in"))
      (node (ref "IC18") (pin "U3") (pinfunction "DAC_GND_U3") (pintype "power_in"))
      (node (ref "IC18") (pin "U30") (pinfunction "GND_U30") (pintype "power_in"))
      (node (ref "IC18") (pin "U32") (pinfunction "GND_U32") (pintype "power_in"))
      (node (ref "IC18") (pin "U36") (pinfunction "GND_U36") (pintype "power_in"))
      (node (ref "IC18") (pin "U37") (pinfunction "GND_U37") (pintype "power_in"))
      (node (ref "IC18") (pin "U6") (pinfunction "DAC_GND_U6") (pintype "power_in"))
      (node (ref "IC18") (pin "U8") (pinfunction "DAC_GND_U8") (pintype "power_in"))
      (node (ref "IC18") (pin "V1") (pinfunction "DAC_GND_V1") (pintype "power_in"))
      (node (ref "IC18") (pin "V10") (pinfunction "DAC_GND_V10") (pintype "power_in"))
      (node (ref "IC18") (pin "V11") (pinfunction "GND_V11") (pintype "power_in"))
      (node (ref "IC18") (pin "V13") (pinfunction "GND_V13") (pintype "power_in"))
      (node (ref "IC18") (pin "V15") (pinfunction "GND_V15") (pintype "power_in"))
      (node (ref "IC18") (pin "V19") (pinfunction "GND_V19") (pintype "power_in"))
      (node (ref "IC18") (pin "V2") (pinfunction "DAC_GND_V2") (pintype "power_in"))
      (node (ref "IC18") (pin "V21") (pinfunction "GND_V21") (pintype "power_in"))
      (node (ref "IC18") (pin "V23") (pinfunction "GND_V23") (pintype "power_in"))
      (node (ref "IC18") (pin "V25") (pinfunction "GND_V25") (pintype "power_in"))
      (node (ref "IC18") (pin "V3") (pinfunction "DAC_GND_V3") (pintype "power_in"))
      (node (ref "IC18") (pin "V30") (pinfunction "GND_V30") (pintype "power_in"))
      (node (ref "IC18") (pin "V34") (pinfunction "GND_V34") (pintype "power_in"))
      (node (ref "IC18") (pin "V37") (pinfunction "GND_V37") (pintype "power_in"))
      (node (ref "IC18") (pin "V38") (pinfunction "GND_V38") (pintype "power_in"))
      (node (ref "IC18") (pin "V39") (pinfunction "GND_V39") (pintype "power_in"))
      (node (ref "IC18") (pin "V4") (pinfunction "DAC_GND_V4") (pintype "power_in"))
      (node (ref "IC18") (pin "V5") (pinfunction "DAC_GND_V5") (pintype "power_in"))
      (node (ref "IC18") (pin "V6") (pinfunction "DAC_GND_V6") (pintype "power_in"))
      (node (ref "IC18") (pin "V7") (pinfunction "DAC_GND_V7") (pintype "power_in"))
      (node (ref "IC18") (pin "V8") (pinfunction "DAC_GND_V8") (pintype "power_in"))
      (node (ref "IC18") (pin "W1") (pinfunction "ADC_GND_W1") (pintype "power_in"))
      (node (ref "IC18") (pin "W10") (pinfunction "DAC_GND_W10") (pintype "power_in"))
      (node (ref "IC18") (pin "W12") (pinfunction "GND_W12") (pintype "power_in"))
      (node (ref "IC18") (pin "W14") (pinfunction "GND_W14") (pintype "power_in"))
      (node (ref "IC18") (pin "W18") (pinfunction "GND_W18") (pintype "power_in"))
      (node (ref "IC18") (pin "W2") (pinfunction "ADC_GND_W2") (pintype "power_in"))
      (node (ref "IC18") (pin "W21") (pinfunction "GND_W21") (pintype "power_in"))
      (node (ref "IC18") (pin "W23") (pinfunction "GND_W23") (pintype "power_in"))
      (node (ref "IC18") (pin "W24") (pinfunction "GND_W24") (pintype "power_in"))
      (node (ref "IC18") (pin "W3") (pinfunction "ADC_GND_W3") (pintype "power_in"))
      (node (ref "IC18") (pin "W30") (pinfunction "GND_W30") (pintype "power_in"))
      (node (ref "IC18") (pin "W32") (pinfunction "GND_W32") (pintype "power_in"))
      (node (ref "IC18") (pin "W36") (pinfunction "GND_W36") (pintype "power_in"))
      (node (ref "IC18") (pin "W37") (pinfunction "GND_W37") (pintype "power_in"))
      (node (ref "IC18") (pin "W4") (pinfunction "ADC_GND_W4") (pintype "power_in"))
      (node (ref "IC18") (pin "W5") (pinfunction "ADC_GND_W5") (pintype "power_in"))
      (node (ref "IC18") (pin "W6") (pinfunction "ADC_GND_W6") (pintype "power_in"))
      (node (ref "IC18") (pin "W7") (pinfunction "DAC_GND_W7") (pintype "power_in"))
      (node (ref "IC18") (pin "Y10") (pinfunction "DAC_GND_Y10") (pintype "power_in"))
      (node (ref "IC18") (pin "Y11") (pinfunction "GND_Y11") (pintype "power_in"))
      (node (ref "IC18") (pin "Y13") (pinfunction "GND_Y13") (pintype "power_in"))
      (node (ref "IC18") (pin "Y15") (pinfunction "GND_Y15") (pintype "power_in"))
      (node (ref "IC18") (pin "Y19") (pinfunction "GND_Y19") (pintype "power_in"))
      (node (ref "IC18") (pin "Y21") (pinfunction "GND_Y21") (pintype "power_in"))
      (node (ref "IC18") (pin "Y23") (pinfunction "GND_Y23") (pintype "power_in"))
      (node (ref "IC18") (pin "Y25") (pinfunction "GND_Y25") (pintype "power_in"))
      (node (ref "IC18") (pin "Y3") (pinfunction "ADC_GND_Y3") (pintype "power_in"))
      (node (ref "IC18") (pin "Y30") (pinfunction "GND_Y30") (pintype "power_in"))
      (node (ref "IC18") (pin "Y34") (pinfunction "GND_Y34") (pintype "power_in"))
      (node (ref "IC18") (pin "Y37") (pinfunction "GND_Y37") (pintype "power_in"))
      (node (ref "IC18") (pin "Y38") (pinfunction "GND_Y38") (pintype "power_in"))
      (node (ref "IC18") (pin "Y39") (pinfunction "GND_Y39") (pintype "power_in"))
      (node (ref "IC18") (pin "Y6") (pinfunction "ADC_GND_Y6") (pintype "power_in"))
      (node (ref "IC18") (pin "Y7") (pinfunction "DAC_GND_Y7") (pintype "power_in"))
      (node (ref "IC18") (pin "Y8") (pinfunction "DAC_GND_Y8") (pintype "power_in"))
      (node (ref "IC18") (pin "Y9") (pinfunction "DAC_GND_Y9") (pintype "power_in"))
    )
    (net (code "2") (name "PS_SYSMON_AGND") (class "Default")
      (node (ref "IC18") (pin "AF29") (pinfunction "GND_PSADC_AF29") (pintype "power_in"))
    )
    (net (code "3") (name "SYSMON_AGND") (class "Default")
      (node (ref "IC18") (pin "V17") (pinfunction "GNDADC_V17") (pintype "power_in"))
    )
  )
)
